# GPRS-Shield-v3_0.net
KiCad netlist of a schematic drawn in EAGLE
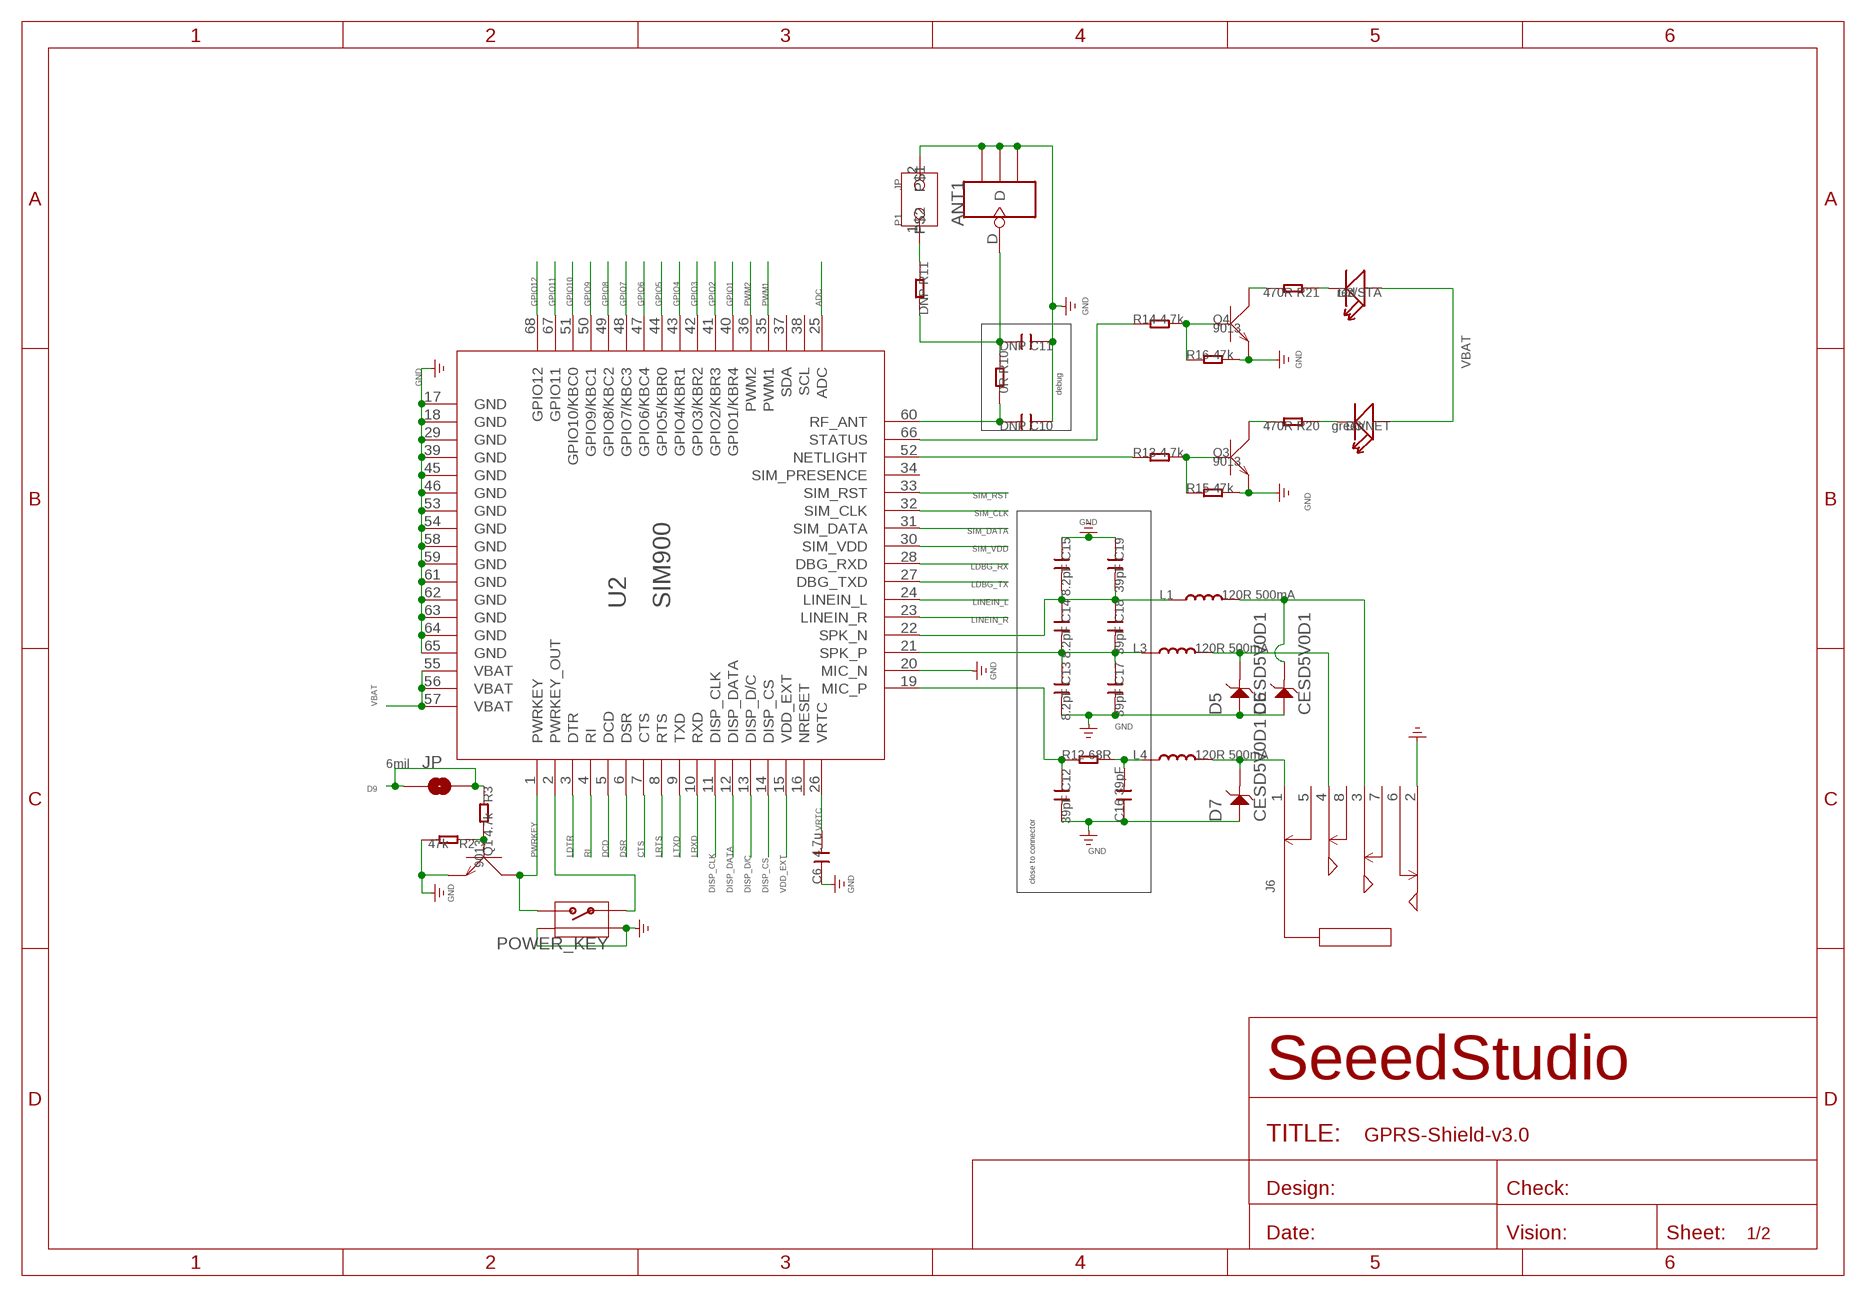
[diagram p0: schematic, sheet 1, part 1 of 2]
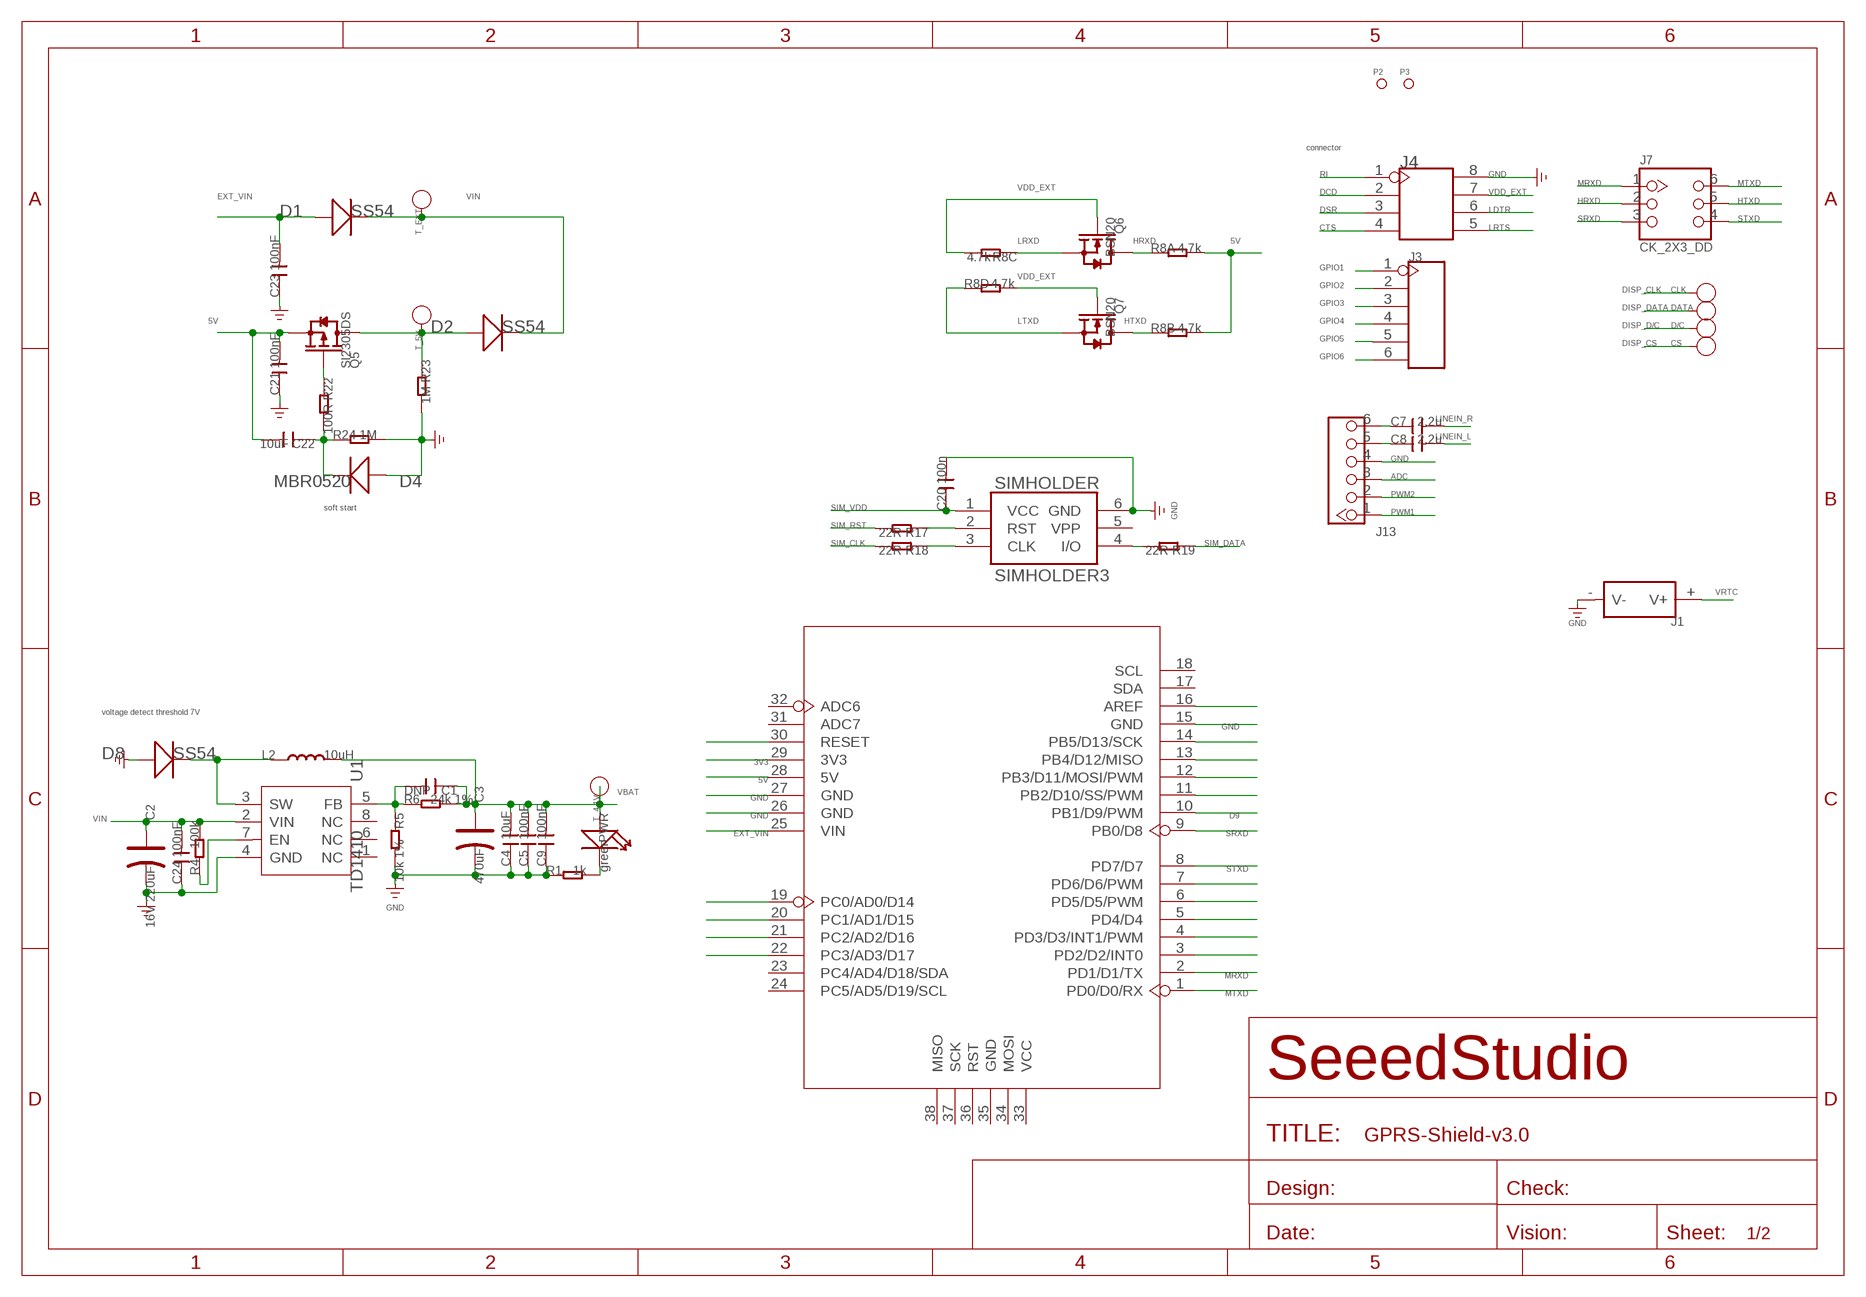
[diagram p1: schematic, sheet 1, part 2 of 2]
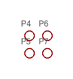
[diagram p2: schematic, sheet 2]

(export (version "E")
  (design (tool "Eeschema 10.0.6"))
  (components
    (comp (ref "ANT1")
      (value "ANTENNA-U-FL")
      (footprint "eagle-import:4P-U-FL")
      (libsource (lib "eagle-import") (part "ANTENNA-U-FL"))
    )
    (comp (ref "C1")
      (value "DNP")
      (footprint "eagle-import:C0603")
      (libsource (lib "eagle-import") (part "C-0603"))
    )
    (comp (ref "C2")
      (value "16V 220uF")
      (footprint "eagle-import:ELECTRO-SMD-D-5.6MM")
      (libsource (lib "eagle-import") (part "CAP-ELECTRO-D"))
    )
    (comp (ref "C3")
      (value "470uF")
      (footprint "eagle-import:AVX-D")
      (libsource (lib "eagle-import") (part "CAP-AVX-D"))
    )
    (comp (ref "C4")
      (value "10uF")
      (footprint "eagle-import:C0805")
      (libsource (lib "eagle-import") (part "C-0805"))
    )
    (comp (ref "C5")
      (value "100nF")
      (footprint "eagle-import:C0603")
      (libsource (lib "eagle-import") (part "C-0603"))
    )
    (comp (ref "C6")
      (value "4.7u")
      (footprint "eagle-import:C0805")
      (libsource (lib "eagle-import") (part "C-0805"))
    )
    (comp (ref "C7")
      (value "2.2u")
      (footprint "eagle-import:C0805")
      (libsource (lib "eagle-import") (part "C-0805"))
    )
    (comp (ref "C8")
      (value "2.2u")
      (footprint "eagle-import:C0805")
      (libsource (lib "eagle-import") (part "C-0805"))
    )
    (comp (ref "C9")
      (value "100nF")
      (footprint "eagle-import:C0603")
      (libsource (lib "eagle-import") (part "C-0603"))
    )
    (comp (ref "C10")
      (value "DNP")
      (footprint "eagle-import:C0603")
      (libsource (lib "eagle-import") (part "C-0603"))
    )
    (comp (ref "C11")
      (value "DNP")
      (footprint "eagle-import:C0603")
      (libsource (lib "eagle-import") (part "C-0603"))
    )
    (comp (ref "C12")
      (value "39pF")
      (footprint "eagle-import:C0603")
      (libsource (lib "eagle-import") (part "C-0603"))
    )
    (comp (ref "C13")
      (value "8.2pF")
      (footprint "eagle-import:C0603")
      (libsource (lib "eagle-import") (part "C-0603"))
    )
    (comp (ref "C14")
      (value "8.2pF")
      (footprint "eagle-import:C0603")
      (libsource (lib "eagle-import") (part "C-0603"))
    )
    (comp (ref "C15")
      (value "8.2pF")
      (footprint "eagle-import:C0603")
      (libsource (lib "eagle-import") (part "C-0603"))
    )
    (comp (ref "C16")
      (value "39pF")
      (footprint "eagle-import:C0603")
      (libsource (lib "eagle-import") (part "C-0603"))
    )
    (comp (ref "C17")
      (value "39pF")
      (footprint "eagle-import:C0603")
      (libsource (lib "eagle-import") (part "C-0603"))
    )
    (comp (ref "C18")
      (value "39pF")
      (footprint "eagle-import:C0603")
      (libsource (lib "eagle-import") (part "C-0603"))
    )
    (comp (ref "C19")
      (value "39pF")
      (footprint "eagle-import:C0603")
      (libsource (lib "eagle-import") (part "C-0603"))
    )
    (comp (ref "C20")
      (value "100n")
      (footprint "eagle-import:C0603")
      (libsource (lib "eagle-import") (part "C-0603"))
    )
    (comp (ref "C21")
      (value "100nF")
      (footprint "eagle-import:C0603")
      (libsource (lib "eagle-import") (part "C-0603"))
    )
    (comp (ref "C22")
      (value "10uF")
      (footprint "eagle-import:C0805")
      (libsource (lib "eagle-import") (part "C-0805"))
    )
    (comp (ref "C23")
      (value "100nF")
      (footprint "eagle-import:C0603")
      (libsource (lib "eagle-import") (part "C-0603"))
    )
    (comp (ref "C24")
      (value "100nF")
      (footprint "eagle-import:C0603")
      (libsource (lib "eagle-import") (part "C-0603"))
    )
    (comp (ref "CLK")
      (value "PAD-TEST-POINT-CIRCLE'4545'")
      (footprint "eagle-import:TP_4545")
      (fields (field (name "PARTNO") "DNP"))
      (libsource (lib "eagle-import") (part "PAD-TEST-POINT-CIRCLE'4545'"))
    )
    (comp (ref "CS")
      (value "PAD-TEST-POINT-CIRCLE'4545'")
      (footprint "eagle-import:TP_4545")
      (fields (field (name "PARTNO") "DNP"))
      (libsource (lib "eagle-import") (part "PAD-TEST-POINT-CIRCLE'4545'"))
    )
    (comp (ref "D/C")
      (value "PAD-TEST-POINT-CIRCLE'4545'")
      (footprint "eagle-import:TP_4545")
      (fields (field (name "PARTNO") "DNP"))
      (libsource (lib "eagle-import") (part "PAD-TEST-POINT-CIRCLE'4545'"))
    )
    (comp (ref "D1")
      (value "SS54")
      (footprint "eagle-import:SMB")
      (libsource (lib "eagle-import") (part "D'MBRS240LT3'"))
    )
    (comp (ref "D2")
      (value "SS54")
      (footprint "eagle-import:SMB")
      (libsource (lib "eagle-import") (part "D'MBRS240LT3'"))
    )
    (comp (ref "D2/STA")
      (value "red")
      (footprint "eagle-import:LED-0603")
      (libsource (lib "eagle-import") (part "LED'0603'"))
    )
    (comp (ref "D3/NET")
      (value "green")
      (footprint "eagle-import:LED-0603")
      (libsource (lib "eagle-import") (part "LED'0603'"))
    )
    (comp (ref "D4")
      (value "MBR0520")
      (footprint "eagle-import:SOD123-2.7X1.6")
      (libsource (lib "eagle-import") (part "D'MBR0520LT1'"))
    )
    (comp (ref "D5")
      (value "CESD5V0D1")
      (footprint "eagle-import:SOD123-2.7X1.6")
      (libsource (lib "eagle-import") (part "D-ESD"))
    )
    (comp (ref "D6")
      (value "CESD5V0D1")
      (footprint "eagle-import:SOD123-2.7X1.6")
      (libsource (lib "eagle-import") (part "D-ESD"))
    )
    (comp (ref "D7")
      (value "CESD5V0D1")
      (footprint "eagle-import:SOD123-2.7X1.6")
      (libsource (lib "eagle-import") (part "D-ESD"))
    )
    (comp (ref "D8")
      (value "SS54")
      (footprint "eagle-import:SMB")
      (libsource (lib "eagle-import") (part "D'MBRS240LT3'"))
    )
    (comp (ref "DATA")
      (value "PAD-TEST-POINT-CIRCLE'4545'")
      (footprint "eagle-import:TP_4545")
      (fields (field (name "PARTNO") "DNP"))
      (libsource (lib "eagle-import") (part "PAD-TEST-POINT-CIRCLE'4545'"))
    )
    (comp (ref "J1")
      (value "HOLDER-BAT")
      (footprint "eagle-import:SMD-CR1220-2")
      (libsource (lib "eagle-import") (part "HOLDER-BAT"))
    )
    (comp (ref "J3")
      (value "HEADER-6P-65/35MIL")
      (footprint "eagle-import:6P-2.54-65_35MIL")
      (libsource (lib "eagle-import") (part "HEADER-6P-65/35MIL"))
    )
    (comp (ref "J4")
      (value "HEADER-2X4P-2.54")
      (footprint "eagle-import:2X4P-2.54")
      (libsource (lib "eagle-import") (part "HEADER-2X4P-2.54"))
    )
    (comp (ref "J6")
      (value "AUDIO-JACK-3.5'PJ-393'")
      (footprint "eagle-import:8P-SMD-3.5")
      (libsource (lib "eagle-import") (part "AUDIO-JACK-3.5'PJ-393'"))
    )
    (comp (ref "J7")
      (value "CK_2X3_DD")
      (footprint "eagle-import:CK_2X3")
      (libsource (lib "eagle-import") (part "CK_2X3_DD"))
    )
    (comp (ref "J13")
      (value "HEADER_1X6")
      (footprint "eagle-import:CK_1X6")
      (libsource (lib "eagle-import") (part "HEADER_1X6"))
    )
    (comp (ref "JP")
      (value "PAD-SOLDERJUMPERNC")
      (footprint "eagle-import:2P-SMD-3.3X2")
      (libsource (lib "eagle-import") (part "PAD-SOLDERJUMPERNC"))
    )
    (comp (ref "L1")
      (value "120R 500mA")
      (footprint "eagle-import:L0603")
      (libsource (lib "eagle-import") (part "L'0603'"))
    )
    (comp (ref "L2")
      (value "10uH")
      (footprint "eagle-import:L0630")
      (libsource (lib "eagle-import") (part "L'0630'"))
    )
    (comp (ref "L3")
      (value "120R 500mA")
      (footprint "eagle-import:L0603")
      (libsource (lib "eagle-import") (part "L'0603'"))
    )
    (comp (ref "L4")
      (value "120R 500mA")
      (footprint "eagle-import:L0603")
      (libsource (lib "eagle-import") (part "L'0603'"))
    )
    (comp (ref "P1") (value "JP") (footprint "eagle-import:JP") (libsource (lib "eagle-import") (part "JP")))
    (comp (ref "P2")
      (value "PAD-MARK")
      (footprint "eagle-import:ROUND-MARK-1.0")
      (fields (field (name "PARTNO") "DNP"))
      (libsource (lib "eagle-import") (part "PAD-MARK"))
    )
    (comp (ref "P3")
      (value "PAD-MARK")
      (footprint "eagle-import:ROUND-MARK-1.0")
      (fields (field (name "PARTNO") "DNP"))
      (libsource (lib "eagle-import") (part "PAD-MARK"))
    )
    (comp (ref "POWER_KEY")
      (value "BUTTON-4P-REINFORCE'TS-118E'")
      (footprint "eagle-import:4P-SMD-7X3.5X3.5H")
      (libsource (lib "eagle-import") (part "BUTTON-4P-REINFORCE'TS-118E'"))
    )
    (comp (ref "PWR")
      (value "green")
      (footprint "eagle-import:D0603")
      (libsource (lib "eagle-import") (part "007-LED0603"))
    )
    (comp (ref "Q1")
      (value "9013")
      (footprint "eagle-import:SOT23")
      (libsource (lib "eagle-import") (part "TRANSISTOR-NPN-SOT23"))
    )
    (comp (ref "Q3")
      (value "9013")
      (footprint "eagle-import:SOT23")
      (libsource (lib "eagle-import") (part "TRANSISTOR-NPN-SOT23"))
    )
    (comp (ref "Q4")
      (value "9013")
      (footprint "eagle-import:SOT23")
      (libsource (lib "eagle-import") (part "TRANSISTOR-NPN-SOT23"))
    )
    (comp (ref "Q5")
      (value "SI2305DS")
      (footprint "eagle-import:SOT23")
      (libsource (lib "eagle-import") (part "MOSFET-P'SI2323CDS/SI2305DS{lt}BR{gt}'"))
    )
    (comp (ref "Q6")
      (value "BSN20")
      (footprint "eagle-import:SOT23")
      (libsource (lib "eagle-import") (part "MOSFET-N'SOT23'"))
    )
    (comp (ref "Q7")
      (value "BSN20")
      (footprint "eagle-import:SOT23")
      (libsource (lib "eagle-import") (part "MOSFET-N'SOT23'"))
    )
    (comp (ref "R1")
      (value "1k")
      (footprint "eagle-import:R0603")
      (libsource (lib "eagle-import") (part "R-0603"))
    )
    (comp (ref "R2")
      (value "47k")
      (footprint "eagle-import:R0603")
      (libsource (lib "eagle-import") (part "R-0603"))
    )
    (comp (ref "R3")
      (value "4.7k")
      (footprint "eagle-import:R0603")
      (libsource (lib "eagle-import") (part "R-0603"))
    )
    (comp (ref "R4")
      (value "100k")
      (footprint "eagle-import:R0603")
      (libsource (lib "eagle-import") (part "R-0603"))
    )
    (comp (ref "R5")
      (value "10k 1%")
      (footprint "eagle-import:R0603")
      (libsource (lib "eagle-import") (part "R-0603"))
    )
    (comp (ref "R6")
      (value "24k 1%")
      (footprint "eagle-import:R0603")
      (libsource (lib "eagle-import") (part "R-0603"))
    )
    (comp (ref "R8")
      (value "4.7k")
      (footprint "eagle-import:1206-8-3.3X2.4")
      (libsource (lib "eagle-import") (part "R-4R-1206"))
    )
    (comp (ref "R10")
      (value "0R")
      (footprint "eagle-import:R0603")
      (libsource (lib "eagle-import") (part "R-0603"))
    )
    (comp (ref "R11")
      (value "DNP")
      (footprint "eagle-import:R0603")
      (libsource (lib "eagle-import") (part "R-0603"))
    )
    (comp (ref "R12")
      (value "68R")
      (footprint "eagle-import:R0603")
      (libsource (lib "eagle-import") (part "R-0603"))
    )
    (comp (ref "R13")
      (value "4.7k")
      (footprint "eagle-import:R0603")
      (libsource (lib "eagle-import") (part "R-0603"))
    )
    (comp (ref "R14")
      (value "4.7k")
      (footprint "eagle-import:R0603")
      (libsource (lib "eagle-import") (part "R-0603"))
    )
    (comp (ref "R15")
      (value "47k")
      (footprint "eagle-import:R0603")
      (libsource (lib "eagle-import") (part "R-0603"))
    )
    (comp (ref "R16")
      (value "47k")
      (footprint "eagle-import:R0603")
      (libsource (lib "eagle-import") (part "R-0603"))
    )
    (comp (ref "R17")
      (value "22R")
      (footprint "eagle-import:R0603")
      (libsource (lib "eagle-import") (part "R-0603"))
    )
    (comp (ref "R18")
      (value "22R")
      (footprint "eagle-import:R0603")
      (libsource (lib "eagle-import") (part "R-0603"))
    )
    (comp (ref "R19")
      (value "22R")
      (footprint "eagle-import:R0603")
      (libsource (lib "eagle-import") (part "R-0603"))
    )
    (comp (ref "R20")
      (value "470R")
      (footprint "eagle-import:R0603")
      (libsource (lib "eagle-import") (part "R-0603"))
    )
    (comp (ref "R21")
      (value "470R")
      (footprint "eagle-import:R0603")
      (libsource (lib "eagle-import") (part "R-0603"))
    )
    (comp (ref "R22")
      (value "100R")
      (footprint "eagle-import:R0603")
      (libsource (lib "eagle-import") (part "R-0603"))
    )
    (comp (ref "R23")
      (value "1M")
      (footprint "eagle-import:R0603")
      (libsource (lib "eagle-import") (part "R-0603"))
    )
    (comp (ref "R24")
      (value "1M")
      (footprint "eagle-import:R0603")
      (libsource (lib "eagle-import") (part "R-0603"))
    )
    (comp (ref "SIMHOLDER")
      (value "SIMHOLDER3")
      (footprint "eagle-import:SIMHOLDER3")
      (libsource (lib "eagle-import") (part "SIMHOLDER3"))
    )
    (comp (ref "T_4.1V")
      (value "PAD-TEST-POINT-CIRCLE'4545'")
      (footprint "eagle-import:TP_4545")
      (fields (field (name "PARTNO") "DNP") (field (name "PARTNO_1") "DNP"))
      (libsource (lib "eagle-import") (part "PAD-TEST-POINT-CIRCLE'4545'"))
    )
    (comp (ref "T_5V")
      (value "PAD-TEST-POINT-CIRCLE'4545'")
      (footprint "eagle-import:TP_4545")
      (fields (field (name "PARTNO") "DNP") (field (name "PARTNO_1") "DNP"))
      (libsource (lib "eagle-import") (part "PAD-TEST-POINT-CIRCLE'4545'"))
    )
    (comp (ref "T_EXT")
      (value "PAD-TEST-POINT-CIRCLE'4545'")
      (footprint "eagle-import:TP_4545")
      (fields (field (name "PARTNO") "DNP") (field (name "PARTNO_1") "DNP"))
      (libsource (lib "eagle-import") (part "PAD-TEST-POINT-CIRCLE'4545'"))
    )
    (comp (ref "U1")
      (value "TD1410")
      (footprint "eagle-import:SOP8")
      (libsource (lib "eagle-import") (part "TD1410"))
    )
    (comp (ref "U2")
      (value "SIM900")
      (footprint "eagle-import:SIM900")
      (libsource (lib "eagle-import") (part "SIM900"))
    )
    (comp (ref "U4")
      (value "ARDUINO-38P'WITH/O-SILK'")
      (footprint "eagle-import:ARDUINO-38P-500519002")
      (libsource (lib "eagle-import") (part "ARDUINO-38P'WITH/O-SILK'"))
    )
    (comp (ref "P4")
      (value "PAD-MARK")
      (footprint "eagle-import:ROUND-MARK-1.0")
      (fields (field (name "PARTNO") "DNP"))
      (libsource (lib "eagle-import") (part "PAD-MARK"))
    )
    (comp (ref "P5")
      (value "PAD-MARK")
      (footprint "eagle-import:ROUND-MARK-1.0")
      (fields (field (name "PARTNO") "DNP"))
      (libsource (lib "eagle-import") (part "PAD-MARK"))
    )
    (comp (ref "P6")
      (value "PAD-MARK")
      (footprint "eagle-import:ROUND-MARK-1.0")
      (fields (field (name "PARTNO") "DNP"))
      (libsource (lib "eagle-import") (part "PAD-MARK"))
    )
    (comp (ref "P7")
      (value "PAD-MARK")
      (footprint "eagle-import:ROUND-MARK-1.0")
      (fields (field (name "PARTNO") "DNP"))
      (libsource (lib "eagle-import") (part "PAD-MARK"))
    )
  )
  (nets
    (net (code "1") (name "3V3") (class "Default")
      (node (ref "U4") (pin "29") (pinfunction "3V3_29") (pintype "bidirectional"))
    )
    (net (code "2") (name "5V") (class "Default")
      (node (ref "C21") (pin "2") (pinfunction "2_2") (pintype "passive"))
      (node (ref "C22") (pin "2") (pinfunction "2_2") (pintype "passive"))
      (node (ref "Q5") (pin "2") (pinfunction "S_2") (pintype "passive"))
      (node (ref "R8") (pin "7") (pinfunction "2_7") (pintype "passive"))
      (node (ref "R8") (pin "8") (pinfunction "2_8") (pintype "passive"))
      (node (ref "U4") (pin "28") (pinfunction "5V_28") (pintype "bidirectional"))
    )
    (net (code "3") (name "ADC") (class "Default")
      (node (ref "J13") (pin "3") (pinfunction "3_3") (pintype "bidirectional"))
      (node (ref "U2") (pin "25") (pinfunction "ADC_25") (pintype "input"))
    )
    (net (code "4") (name "CTS") (class "Default")
      (node (ref "J4") (pin "4") (pinfunction "4_4") (pintype "bidirectional"))
      (node (ref "U2") (pin "7") (pinfunction "CTS_7") (pintype "output"))
    )
    (net (code "5") (name "D9") (class "Default")
      (node (ref "JP") (pin "1") (pinfunction "1_1") (pintype "passive"))
      (node (ref "JP") (pin "2") (pinfunction "2_2") (pintype "passive"))
      (node (ref "R3") (pin "1") (pinfunction "1_1") (pintype "passive"))
      (node (ref "U4") (pin "10") (pinfunction "PB1/D9/PWM_10") (pintype "bidirectional"))
    )
    (net (code "6") (name "DCD") (class "Default")
      (node (ref "J4") (pin "2") (pinfunction "2_2") (pintype "bidirectional"))
      (node (ref "U2") (pin "5") (pinfunction "DCD_5") (pintype "output"))
    )
    (net (code "7") (name "DISP_CLK") (class "Default")
      (node (ref "CLK") (pin "T") (pinfunction "T_T") (pintype "bidirectional"))
      (node (ref "U2") (pin "11") (pinfunction "DISP_CLK_11") (pintype "output"))
    )
    (net (code "8") (name "DISP_CS") (class "Default")
      (node (ref "CS") (pin "T") (pinfunction "T_T") (pintype "bidirectional"))
      (node (ref "U2") (pin "14") (pinfunction "DISP_CS_14") (pintype "output"))
    )
    (net (code "9") (name "DISP_DATA") (class "Default")
      (node (ref "DATA") (pin "T") (pinfunction "T_T") (pintype "bidirectional"))
      (node (ref "U2") (pin "12") (pinfunction "DISP_DATA_12") (pintype "bidirectional"))
    )
    (net (code "10") (name "DISP_D{slash}C") (class "Default")
      (node (ref "D/C") (pin "T") (pinfunction "T_T") (pintype "bidirectional"))
      (node (ref "U2") (pin "13") (pinfunction "DISP_D/C_13") (pintype "output"))
    )
    (net (code "11") (name "DSR") (class "Default")
      (node (ref "J4") (pin "3") (pinfunction "3_3") (pintype "bidirectional"))
      (node (ref "U2") (pin "6") (pinfunction "DSR_6") (pintype "output"))
    )
    (net (code "12") (name "EXT_VIN") (class "Default")
      (node (ref "C23") (pin "2") (pinfunction "2_2") (pintype "passive"))
      (node (ref "D1") (pin "+") (pinfunction "+_+") (pintype "passive"))
      (node (ref "U4") (pin "25") (pinfunction "VIN_25") (pintype "bidirectional"))
    )
    (net (code "13") (name "GND") (class "Default")
      (node (ref "ANT1") (pin "GND1") (pinfunction "GND1_GND1") (pintype "bidirectional"))
      (node (ref "ANT1") (pin "GND2") (pinfunction "GND2_GND2") (pintype "bidirectional"))
      (node (ref "ANT1") (pin "GND3") (pinfunction "GND3_GND3") (pintype "bidirectional"))
      (node (ref "C10") (pin "1") (pinfunction "1_1") (pintype "passive"))
      (node (ref "C11") (pin "1") (pinfunction "1_1") (pintype "passive"))
      (node (ref "C12") (pin "2") (pinfunction "2_2") (pintype "passive"))
      (node (ref "C13") (pin "2") (pinfunction "2_2") (pintype "passive"))
      (node (ref "C15") (pin "1") (pinfunction "1_1") (pintype "passive"))
      (node (ref "C16") (pin "1") (pinfunction "1_1") (pintype "passive"))
      (node (ref "C17") (pin "2") (pinfunction "2_2") (pintype "passive"))
      (node (ref "C19") (pin "1") (pinfunction "1_1") (pintype "passive"))
      (node (ref "C2") (pin "-") (pinfunction "-_-") (pintype "passive"))
      (node (ref "C20") (pin "2") (pinfunction "2_2") (pintype "passive"))
      (node (ref "C21") (pin "1") (pinfunction "1_1") (pintype "passive"))
      (node (ref "C23") (pin "1") (pinfunction "1_1") (pintype "passive"))
      (node (ref "C24") (pin "1") (pinfunction "1_1") (pintype "passive"))
      (node (ref "C3") (pin "-") (pinfunction "-_-") (pintype "passive"))
      (node (ref "C4") (pin "1") (pinfunction "1_1") (pintype "passive"))
      (node (ref "C5") (pin "1") (pinfunction "1_1") (pintype "passive"))
      (node (ref "C6") (pin "1") (pinfunction "1_1") (pintype "passive"))
      (node (ref "C9") (pin "1") (pinfunction "1_1") (pintype "passive"))
      (node (ref "D4") (pin "1") (pinfunction "+_1") (pintype "passive"))
      (node (ref "D5") (pin "1") (pinfunction "1_1") (pintype "bidirectional"))
      (node (ref "D6") (pin "1") (pinfunction "1_1") (pintype "bidirectional"))
      (node (ref "D7") (pin "1") (pinfunction "1_1") (pintype "bidirectional"))
      (node (ref "D8") (pin "+") (pinfunction "+_+") (pintype "passive"))
      (node (ref "J1") (pin "-") (pinfunction "V-_-") (pintype "bidirectional"))
      (node (ref "J13") (pin "4") (pinfunction "4_4") (pintype "bidirectional"))
      (node (ref "J4") (pin "8") (pinfunction "8_8") (pintype "bidirectional"))
      (node (ref "J6") (pin "2") (pinfunction "2_2") (pintype "bidirectional"))
      (node (ref "P1") (pin "2") (pinfunction "P$2_2") (pintype "bidirectional"))
      (node (ref "POWER_KEY") (pin "S1") (pinfunction "S1_S1") (pintype "bidirectional"))
      (node (ref "POWER_KEY") (pin "S2") (pinfunction "S2_S2") (pintype "bidirectional"))
      (node (ref "Q1") (pin "2") (pinfunction "E_2") (pintype "passive"))
      (node (ref "Q3") (pin "2") (pinfunction "E_2") (pintype "passive"))
      (node (ref "Q4") (pin "2") (pinfunction "E_2") (pintype "passive"))
      (node (ref "R1") (pin "1") (pinfunction "1_1") (pintype "passive"))
      (node (ref "R15") (pin "2") (pinfunction "2_2") (pintype "passive"))
      (node (ref "R16") (pin "2") (pinfunction "2_2") (pintype "passive"))
      (node (ref "R2") (pin "2") (pinfunction "2_2") (pintype "passive"))
      (node (ref "R23") (pin "2") (pinfunction "2_2") (pintype "passive"))
      (node (ref "R24") (pin "2") (pinfunction "2_2") (pintype "passive"))
      (node (ref "R5") (pin "2") (pinfunction "2_2") (pintype "passive"))
      (node (ref "SIMHOLDER") (pin "6") (pinfunction "GND_6") (pintype "bidirectional"))
      (node (ref "U1") (pin "4") (pinfunction "GND_4") (pintype "power_in"))
      (node (ref "U2") (pin "17") (pinfunction "GND_17") (pintype "power_in"))
      (node (ref "U2") (pin "18") (pinfunction "GND_18") (pintype "power_in"))
      (node (ref "U2") (pin "20") (pinfunction "MIC_N_20") (pintype "input"))
      (node (ref "U2") (pin "29") (pinfunction "GND_29") (pintype "power_in"))
      (node (ref "U2") (pin "39") (pinfunction "GND_39") (pintype "power_in"))
      (node (ref "U2") (pin "45") (pinfunction "GND_45") (pintype "power_in"))
      (node (ref "U2") (pin "46") (pinfunction "GND_46") (pintype "power_in"))
      (node (ref "U2") (pin "53") (pinfunction "GND_53") (pintype "power_in"))
      (node (ref "U2") (pin "54") (pinfunction "GND_54") (pintype "power_in"))
      (node (ref "U2") (pin "58") (pinfunction "GND_58") (pintype "power_in"))
      (node (ref "U2") (pin "59") (pinfunction "GND_59") (pintype "power_in"))
      (node (ref "U2") (pin "61") (pinfunction "GND_61") (pintype "power_in"))
      (node (ref "U2") (pin "62") (pinfunction "GND_62") (pintype "power_in"))
      (node (ref "U2") (pin "63") (pinfunction "GND_63") (pintype "power_in"))
      (node (ref "U2") (pin "64") (pinfunction "GND_64") (pintype "power_in"))
      (node (ref "U2") (pin "65") (pinfunction "GND_65") (pintype "power_in"))
      (node (ref "U4") (pin "15") (pinfunction "GND_15") (pintype "bidirectional"))
      (node (ref "U4") (pin "26") (pinfunction "GND_26") (pintype "bidirectional"))
      (node (ref "U4") (pin "27") (pinfunction "GND_27") (pintype "bidirectional"))
    )
    (net (code "14") (name "GPIO1") (class "Default")
      (node (ref "J3") (pin "1") (pinfunction "1_1") (pintype "bidirectional"))
      (node (ref "U2") (pin "40") (pinfunction "GPIO1/KBR4_40") (pintype "output"))
    )
    (net (code "15") (name "GPIO2") (class "Default")
      (node (ref "J3") (pin "2") (pinfunction "2_2") (pintype "bidirectional"))
      (node (ref "U2") (pin "41") (pinfunction "GPIO2/KBR3_41") (pintype "output"))
    )
    (net (code "16") (name "GPIO3") (class "Default")
      (node (ref "J3") (pin "3") (pinfunction "3_3") (pintype "bidirectional"))
      (node (ref "U2") (pin "42") (pinfunction "GPIO3/KBR2_42") (pintype "output"))
    )
    (net (code "17") (name "GPIO4") (class "Default")
      (node (ref "J3") (pin "4") (pinfunction "4_4") (pintype "bidirectional"))
      (node (ref "U2") (pin "43") (pinfunction "GPIO4/KBR1_43") (pintype "output"))
    )
    (net (code "18") (name "GPIO5") (class "Default")
      (node (ref "J3") (pin "5") (pinfunction "5_5") (pintype "bidirectional"))
      (node (ref "U2") (pin "44") (pinfunction "GPIO5/KBR0_44") (pintype "output"))
    )
    (net (code "19") (name "GPIO6") (class "Default")
      (node (ref "J3") (pin "6") (pinfunction "6_6") (pintype "bidirectional"))
      (node (ref "U2") (pin "47") (pinfunction "GPIO6/KBC4_47") (pintype "input"))
    )
    (net (code "20") (name "GPIO7") (class "Default")
      (node (ref "U2") (pin "48") (pinfunction "GPIO7/KBC3_48") (pintype "bidirectional"))
    )
    (net (code "21") (name "GPIO8") (class "Default")
      (node (ref "U2") (pin "49") (pinfunction "GPIO8/KBC2_49") (pintype "input"))
    )
    (net (code "22") (name "GPIO9") (class "Default")
      (node (ref "U2") (pin "50") (pinfunction "GPIO9/KBC1_50") (pintype "input"))
    )
    (net (code "23") (name "GPIO10") (class "Default")
      (node (ref "U2") (pin "51") (pinfunction "GPIO10/KBC0_51") (pintype "bidirectional"))
    )
    (net (code "24") (name "GPIO11") (class "Default")
      (node (ref "U2") (pin "67") (pinfunction "GPIO11_67") (pintype "bidirectional"))
    )
    (net (code "25") (name "GPIO12") (class "Default")
      (node (ref "U2") (pin "68") (pinfunction "GPIO12_68") (pintype "bidirectional"))
    )
    (net (code "26") (name "HRXD") (class "Default")
      (node (ref "J7") (pin "2") (pinfunction "2_2") (pintype "bidirectional"))
      (node (ref "Q6") (pin "3") (pinfunction "D_3") (pintype "passive"))
      (node (ref "R8") (pin "1") (pinfunction "1_1") (pintype "passive"))
    )
    (net (code "27") (name "HTXD") (class "Default")
      (node (ref "J7") (pin "5") (pinfunction "5_5") (pintype "bidirectional"))
      (node (ref "Q7") (pin "3") (pinfunction "D_3") (pintype "passive"))
      (node (ref "R8") (pin "2") (pinfunction "1_2") (pintype "passive"))
    )
    (net (code "28") (name "LDBG_RX") (class "Default")
      (node (ref "U2") (pin "28") (pinfunction "DBG_RXD_28") (pintype "input"))
    )
    (net (code "29") (name "LDBG_TX") (class "Default")
      (node (ref "U2") (pin "27") (pinfunction "DBG_TXD_27") (pintype "output"))
    )
    (net (code "30") (name "LDTR") (class "Default")
      (node (ref "J4") (pin "6") (pinfunction "6_6") (pintype "bidirectional"))
      (node (ref "U2") (pin "3") (pinfunction "DTR_3") (pintype "input"))
    )
    (net (code "31") (name "LINEIN_L") (class "Default")
      (node (ref "C8") (pin "2") (pinfunction "2_2") (pintype "passive"))
      (node (ref "U2") (pin "24") (pinfunction "LINEIN_L_24") (pintype "input"))
    )
    (net (code "32") (name "LINEIN_R") (class "Default")
      (node (ref "C7") (pin "2") (pinfunction "2_2") (pintype "passive"))
      (node (ref "U2") (pin "23") (pinfunction "LINEIN_R_23") (pintype "input"))
    )
    (net (code "33") (name "LRTS") (class "Default")
      (node (ref "J4") (pin "5") (pinfunction "5_5") (pintype "bidirectional"))
      (node (ref "U2") (pin "8") (pinfunction "RTS_8") (pintype "input"))
    )
    (net (code "34") (name "LRXD") (class "Default")
      (node (ref "Q6") (pin "2") (pinfunction "S_2") (pintype "passive"))
      (node (ref "R8") (pin "3") (pinfunction "1_3") (pintype "passive"))
      (node (ref "U2") (pin "10") (pinfunction "RXD_10") (pintype "input"))
    )
    (net (code "35") (name "LTXD") (class "Default")
      (node (ref "Q7") (pin "2") (pinfunction "S_2") (pintype "passive"))
      (node (ref "R8") (pin "4") (pinfunction "1_4") (pintype "passive"))
      (node (ref "U2") (pin "9") (pinfunction "TXD_9") (pintype "output"))
    )
    (net (code "36") (name "MRXD") (class "Default")
      (node (ref "J7") (pin "1") (pinfunction "1_1") (pintype "bidirectional"))
      (node (ref "U4") (pin "2") (pinfunction "PD1/D1/TX_2") (pintype "bidirectional"))
    )
    (net (code "37") (name "MTXD") (class "Default")
      (node (ref "J7") (pin "6") (pinfunction "6_6") (pintype "bidirectional"))
      (node (ref "U4") (pin "1") (pinfunction "PD0/D0/RX_1") (pintype "bidirectional"))
    )
    (net (code "38") (name "Net-(ANT1-PadD)") (class "Default")
      (node (ref "ANT1") (pin "D") (pinfunction "D_D") (pintype "bidirectional"))
      (node (ref "C11") (pin "2") (pinfunction "2_2") (pintype "passive"))
      (node (ref "R10") (pin "1") (pinfunction "1_1") (pintype "passive"))
      (node (ref "R11") (pin "2") (pinfunction "2_2") (pintype "passive"))
    )
    (net (code "39") (name "Net-(C7-Pad1)") (class "Default")
      (node (ref "C7") (pin "1") (pinfunction "1_1") (pintype "passive"))
      (node (ref "J13") (pin "6") (pinfunction "6_6") (pintype "bidirectional"))
    )
    (net (code "40") (name "Net-(C8-Pad1)") (class "Default")
      (node (ref "C8") (pin "1") (pinfunction "1_1") (pintype "passive"))
      (node (ref "J13") (pin "5") (pinfunction "5_5") (pintype "bidirectional"))
    )
    (net (code "41") (name "Net-(C16-Pad2)") (class "Default")
      (node (ref "C16") (pin "2") (pinfunction "2_2") (pintype "passive"))
      (node (ref "L4") (pin "1") (pinfunction "1_1") (pintype "passive"))
      (node (ref "R12") (pin "2") (pinfunction "2_2") (pintype "passive"))
    )
    (net (code "42") (name "Net-(D2/STA-Pad-)") (class "Default")
      (node (ref "D2/STA") (pin "-") (pinfunction "-_-") (pintype "passive"))
      (node (ref "R21") (pin "1") (pinfunction "1_1") (pintype "passive"))
    )
    (net (code "43") (name "Net-(D3/NET-Pad-)") (class "Default")
      (node (ref "D3/NET") (pin "-") (pinfunction "-_-") (pintype "passive"))
      (node (ref "R20") (pin "1") (pinfunction "1_1") (pintype "passive"))
    )
    (net (code "44") (name "Net-(D4--)") (class "Default")
      (node (ref "C22") (pin "1") (pinfunction "1_1") (pintype "passive"))
      (node (ref "D4") (pin "2") (pinfunction "-_2") (pintype "passive"))
      (node (ref "R22") (pin "2") (pinfunction "2_2") (pintype "passive"))
      (node (ref "R24") (pin "1") (pinfunction "1_1") (pintype "passive"))
    )
    (net (code "45") (name "Net-(D5-Pad2)") (class "Default")
      (node (ref "D5") (pin "2") (pinfunction "2_2") (pintype "bidirectional"))
      (node (ref "J6") (pin "4") (pinfunction "4_4") (pintype "bidirectional"))
      (node (ref "L3") (pin "2") (pinfunction "2_2") (pintype "passive"))
    )
    (net (code "46") (name "Net-(D6-Pad2)") (class "Default")
      (node (ref "D6") (pin "2") (pinfunction "2_2") (pintype "bidirectional"))
      (node (ref "J6") (pin "3") (pinfunction "3_3") (pintype "bidirectional"))
      (node (ref "L1") (pin "2") (pinfunction "2_2") (pintype "passive"))
    )
    (net (code "47") (name "Net-(D7-Pad2)") (class "Default")
      (node (ref "D7") (pin "2") (pinfunction "2_2") (pintype "bidirectional"))
      (node (ref "J6") (pin "1") (pinfunction "1_1") (pintype "bidirectional"))
      (node (ref "L4") (pin "2") (pinfunction "2_2") (pintype "passive"))
    )
    (net (code "48") (name "Net-(P1-P$1)") (class "Default")
      (node (ref "P1") (pin "1") (pinfunction "P$1_1") (pintype "bidirectional"))
      (node (ref "R11") (pin "1") (pinfunction "1_1") (pintype "passive"))
    )
    (net (code "49") (name "Net-(PWR-Pad-)") (class "Default")
      (node (ref "PWR") (pin "-") (pinfunction "-_-") (pintype "passive"))
      (node (ref "R1") (pin "2") (pinfunction "2_2") (pintype "passive"))
    )
    (net (code "50") (name "Net-(Q1-B)") (class "Default")
      (node (ref "Q1") (pin "1") (pinfunction "B_1") (pintype "passive"))
      (node (ref "R2") (pin "1") (pinfunction "1_1") (pintype "passive"))
      (node (ref "R3") (pin "2") (pinfunction "2_2") (pintype "passive"))
    )
    (net (code "51") (name "Net-(Q3-B)") (class "Default")
      (node (ref "Q3") (pin "1") (pinfunction "B_1") (pintype "passive"))
      (node (ref "R13") (pin "2") (pinfunction "2_2") (pintype "passive"))
      (node (ref "R15") (pin "1") (pinfunction "1_1") (pintype "passive"))
    )
    (net (code "52") (name "Net-(Q3-C)") (class "Default")
      (node (ref "Q3") (pin "3") (pinfunction "C_3") (pintype "passive"))
      (node (ref "R20") (pin "2") (pinfunction "2_2") (pintype "passive"))
    )
    (net (code "53") (name "Net-(Q4-B)") (class "Default")
      (node (ref "Q4") (pin "1") (pinfunction "B_1") (pintype "passive"))
      (node (ref "R14") (pin "2") (pinfunction "2_2") (pintype "passive"))
      (node (ref "R16") (pin "1") (pinfunction "1_1") (pintype "passive"))
    )
    (net (code "54") (name "Net-(Q4-C)") (class "Default")
      (node (ref "Q4") (pin "3") (pinfunction "C_3") (pintype "passive"))
      (node (ref "R21") (pin "2") (pinfunction "2_2") (pintype "passive"))
    )
    (net (code "55") (name "Net-(Q5-D)") (class "Default")
      (node (ref "D2") (pin "+") (pinfunction "+_+") (pintype "passive"))
      (node (ref "Q5") (pin "3") (pinfunction "D_3") (pintype "passive"))
      (node (ref "R23") (pin "1") (pinfunction "1_1") (pintype "passive"))
      (node (ref "T_5V") (pin "T") (pinfunction "T_T") (pintype "bidirectional"))
    )
    (net (code "56") (name "Net-(Q5-G)") (class "Default")
      (node (ref "Q5") (pin "1") (pinfunction "G_1") (pintype "passive"))
      (node (ref "R22") (pin "1") (pinfunction "1_1") (pintype "passive"))
    )
    (net (code "57") (name "Net-(SIMHOLDER-CLK)") (class "Default")
      (node (ref "R18") (pin "1") (pinfunction "1_1") (pintype "passive"))
      (node (ref "SIMHOLDER") (pin "3") (pinfunction "CLK_3") (pintype "bidirectional"))
    )
    (net (code "58") (name "Net-(SIMHOLDER-I{slash}O)") (class "Default")
      (node (ref "R19") (pin "2") (pinfunction "2_2") (pintype "passive"))
      (node (ref "SIMHOLDER") (pin "4") (pinfunction "I/O_4") (pintype "bidirectional"))
    )
    (net (code "59") (name "Net-(SIMHOLDER-RST)") (class "Default")
      (node (ref "R17") (pin "1") (pinfunction "1_1") (pintype "passive"))
      (node (ref "SIMHOLDER") (pin "2") (pinfunction "RST_2") (pintype "bidirectional"))
    )
    (net (code "60") (name "Net-(U1-EN)") (class "Default")
      (node (ref "R4") (pin "1") (pinfunction "1_1") (pintype "passive"))
      (node (ref "U1") (pin "7") (pinfunction "EN_7") (pintype "input"))
    )
    (net (code "61") (name "Net-(U1-FB)") (class "Default")
      (node (ref "C1") (pin "2") (pinfunction "2_2") (pintype "passive"))
      (node (ref "R5") (pin "1") (pinfunction "1_1") (pintype "passive"))
      (node (ref "R6") (pin "1") (pinfunction "1_1") (pintype "passive"))
      (node (ref "U1") (pin "5") (pinfunction "FB_5") (pintype "input"))
    )
    (net (code "62") (name "Net-(U1-SW)") (class "Default")
      (node (ref "D8") (pin "-") (pinfunction "-_-") (pintype "passive"))
      (node (ref "L2") (pin "1") (pinfunction "1_1") (pintype "passive"))
      (node (ref "U1") (pin "3") (pinfunction "SW_3") (pintype "output"))
    )
    (net (code "63") (name "Net-(U2-MIC_P)") (class "Default")
      (node (ref "C12") (pin "1") (pinfunction "1_1") (pintype "passive"))
      (node (ref "R12") (pin "1") (pinfunction "1_1") (pintype "passive"))
      (node (ref "U2") (pin "19") (pinfunction "MIC_P_19") (pintype "input"))
    )
    (net (code "64") (name "Net-(U2-NETLIGHT)") (class "Default")
      (node (ref "R13") (pin "1") (pinfunction "1_1") (pintype "passive"))
      (node (ref "U2") (pin "52") (pinfunction "NETLIGHT_52") (pintype "output"))
    )
    (net (code "65") (name "Net-(U2-PWRKEY_OUT)") (class "Default")
      (node (ref "POWER_KEY") (pin "1") (pinfunction "1_1") (pintype "bidirectional"))
      (node (ref "U2") (pin "2") (pinfunction "PWRKEY_OUT_2") (pintype "output"))
    )
    (net (code "66") (name "Net-(U2-RF_ANT)") (class "Default")
      (node (ref "C10") (pin "2") (pinfunction "2_2") (pintype "passive"))
      (node (ref "R10") (pin "2") (pinfunction "2_2") (pintype "passive"))
      (node (ref "U2") (pin "60") (pinfunction "RF_ANT_60") (pintype "bidirectional"))
    )
    (net (code "67") (name "Net-(U2-SPK_N)") (class "Default")
      (node (ref "C14") (pin "1") (pinfunction "1_1") (pintype "passive"))
      (node (ref "C15") (pin "2") (pinfunction "2_2") (pintype "passive"))
      (node (ref "C18") (pin "1") (pinfunction "1_1") (pintype "passive"))
      (node (ref "C19") (pin "2") (pinfunction "2_2") (pintype "passive"))
      (node (ref "L1") (pin "1") (pinfunction "1_1") (pintype "passive"))
      (node (ref "U2") (pin "22") (pinfunction "SPK_N_22") (pintype "output"))
    )
    (net (code "68") (name "Net-(U2-SPK_P)") (class "Default")
      (node (ref "C13") (pin "1") (pinfunction "1_1") (pintype "passive"))
      (node (ref "C14") (pin "2") (pinfunction "2_2") (pintype "passive"))
      (node (ref "C17") (pin "1") (pinfunction "1_1") (pintype "passive"))
      (node (ref "C18") (pin "2") (pinfunction "2_2") (pintype "passive"))
      (node (ref "L3") (pin "1") (pinfunction "1_1") (pintype "passive"))
      (node (ref "U2") (pin "21") (pinfunction "SPK_P_21") (pintype "output"))
    )
    (net (code "69") (name "Net-(U2-STATUS)") (class "Default")
      (node (ref "R14") (pin "1") (pinfunction "1_1") (pintype "passive"))
      (node (ref "U2") (pin "66") (pinfunction "STATUS_66") (pintype "output"))
    )
    (net (code "70") (name "PWM1") (class "Default")
      (node (ref "J13") (pin "1") (pinfunction "1_1") (pintype "bidirectional"))
      (node (ref "U2") (pin "35") (pinfunction "PWM1_35") (pintype "output"))
    )
    (net (code "71") (name "PWM2") (class "Default")
      (node (ref "J13") (pin "2") (pinfunction "2_2") (pintype "bidirectional"))
      (node (ref "U2") (pin "36") (pinfunction "PWM2_36") (pintype "output"))
    )
    (net (code "72") (name "PWRKEY") (class "Default")
      (node (ref "POWER_KEY") (pin "2") (pinfunction "2_2") (pintype "bidirectional"))
      (node (ref "Q1") (pin "3") (pinfunction "C_3") (pintype "passive"))
      (node (ref "U2") (pin "1") (pinfunction "PWRKEY_1") (pintype "input"))
    )
    (net (code "73") (name "RI") (class "Default")
      (node (ref "J4") (pin "1") (pinfunction "1_1") (pintype "bidirectional"))
      (node (ref "U2") (pin "4") (pinfunction "RI_4") (pintype "output"))
    )
    (net (code "74") (name "SIM_CLK") (class "Default")
      (node (ref "R18") (pin "2") (pinfunction "2_2") (pintype "passive"))
      (node (ref "U2") (pin "32") (pinfunction "SIM_CLK_32") (pintype "output"))
    )
    (net (code "75") (name "SIM_DATA") (class "Default")
      (node (ref "R19") (pin "1") (pinfunction "1_1") (pintype "passive"))
      (node (ref "U2") (pin "31") (pinfunction "SIM_DATA_31") (pintype "bidirectional"))
    )
    (net (code "76") (name "SIM_RST") (class "Default")
      (node (ref "R17") (pin "2") (pinfunction "2_2") (pintype "passive"))
      (node (ref "U2") (pin "33") (pinfunction "SIM_RST_33") (pintype "output"))
    )
    (net (code "77") (name "SIM_VDD") (class "Default")
      (node (ref "C20") (pin "1") (pinfunction "1_1") (pintype "passive"))
      (node (ref "SIMHOLDER") (pin "1") (pinfunction "VCC_1") (pintype "bidirectional"))
      (node (ref "U2") (pin "30") (pinfunction "SIM_VDD_30") (pintype "output"))
    )
    (net (code "78") (name "SRXD") (class "Default")
      (node (ref "J7") (pin "3") (pinfunction "3_3") (pintype "bidirectional"))
      (node (ref "U4") (pin "9") (pinfunction "PB0/D8_9") (pintype "bidirectional"))
    )
    (net (code "79") (name "STXD") (class "Default")
      (node (ref "J7") (pin "4") (pinfunction "4_4") (pintype "bidirectional"))
      (node (ref "U4") (pin "8") (pinfunction "PD7/D7_8") (pintype "bidirectional"))
    )
    (net (code "80") (name "VBAT") (class "Default")
      (node (ref "C1") (pin "1") (pinfunction "1_1") (pintype "passive"))
      (node (ref "C3") (pin "+") (pinfunction "+_+") (pintype "passive"))
      (node (ref "C4") (pin "2") (pinfunction "2_2") (pintype "passive"))
      (node (ref "C5") (pin "2") (pinfunction "2_2") (pintype "passive"))
      (node (ref "C9") (pin "2") (pinfunction "2_2") (pintype "passive"))
      (node (ref "D2/STA") (pin "+") (pinfunction "+_+") (pintype "passive"))
      (node (ref "D3/NET") (pin "+") (pinfunction "+_+") (pintype "passive"))
      (node (ref "L2") (pin "2") (pinfunction "2_2") (pintype "passive"))
      (node (ref "PWR") (pin "+") (pinfunction "+_+") (pintype "passive"))
      (node (ref "R6") (pin "2") (pinfunction "2_2") (pintype "passive"))
      (node (ref "T_4.1V") (pin "T") (pinfunction "T_T") (pintype "bidirectional"))
      (node (ref "U2") (pin "55") (pinfunction "VBAT_55") (pintype "power_in"))
      (node (ref "U2") (pin "56") (pinfunction "VBAT_56") (pintype "power_in"))
      (node (ref "U2") (pin "57") (pinfunction "VBAT_57") (pintype "power_in"))
    )
    (net (code "81") (name "VDD_EXT") (class "Default")
      (node (ref "J4") (pin "7") (pinfunction "7_7") (pintype "bidirectional"))
      (node (ref "Q6") (pin "1") (pinfunction "G_1") (pintype "passive"))
      (node (ref "Q7") (pin "1") (pinfunction "G_1") (pintype "passive"))
      (node (ref "R8") (pin "5") (pinfunction "2_5") (pintype "passive"))
      (node (ref "R8") (pin "6") (pinfunction "2_6") (pintype "passive"))
      (node (ref "U2") (pin "15") (pinfunction "VDD_EXT_15") (pintype "output"))
    )
    (net (code "82") (name "VIN") (class "Default")
      (node (ref "C2") (pin "+") (pinfunction "+_+") (pintype "passive"))
      (node (ref "C24") (pin "2") (pinfunction "2_2") (pintype "passive"))
      (node (ref "D1") (pin "-") (pinfunction "-_-") (pintype "passive"))
      (node (ref "D2") (pin "-") (pinfunction "-_-") (pintype "passive"))
      (node (ref "R4") (pin "2") (pinfunction "2_2") (pintype "passive"))
      (node (ref "T_EXT") (pin "T") (pinfunction "T_T") (pintype "bidirectional"))
      (node (ref "U1") (pin "2") (pinfunction "VIN_2") (pintype "input"))
    )
    (net (code "83") (name "VRTC") (class "Default")
      (node (ref "C6") (pin "2") (pinfunction "2_2") (pintype "passive"))
      (node (ref "J1") (pin "+") (pinfunction "V+_+") (pintype "bidirectional"))
      (node (ref "U2") (pin "26") (pinfunction "VRTC_26") (pintype "bidirectional"))
    )
    (net (code "84") (name "unconnected-(J6-Pad5)") (class "Default")
      (node (ref "J6") (pin "5") (pinfunction "5_5") (pintype "bidirectional"))
    )
    (net (code "85") (name "unconnected-(J6-Pad6)") (class "Default")
      (node (ref "J6") (pin "6") (pinfunction "6_6") (pintype "bidirectional"))
    )
    (net (code "86") (name "unconnected-(J6-Pad7)") (class "Default")
      (node (ref "J6") (pin "7") (pinfunction "7_7") (pintype "bidirectional"))
    )
    (net (code "87") (name "unconnected-(J6-Pad8)") (class "Default")
      (node (ref "J6") (pin "8") (pinfunction "8_8") (pintype "bidirectional"))
    )
    (net (code "88") (name "unconnected-(SIMHOLDER-VPP-Pad5)") (class "Default")
      (node (ref "SIMHOLDER") (pin "5") (pinfunction "VPP_5") (pintype "bidirectional"))
    )
    (net (code "89") (name "unconnected-(U1-NC-Pad1)") (class "Default")
      (node (ref "U1") (pin "1") (pinfunction "NC_1") (pintype "no_connect"))
    )
    (net (code "90") (name "unconnected-(U1-NC-Pad6)") (class "Default")
      (node (ref "U1") (pin "6") (pinfunction "NC_6") (pintype "no_connect"))
    )
    (net (code "91") (name "unconnected-(U1-NC-Pad8)") (class "Default")
      (node (ref "U1") (pin "8") (pinfunction "NC_8") (pintype "no_connect"))
    )
    (net (code "92") (name "unconnected-(U2-NRESET-Pad16)") (class "Default")
      (node (ref "U2") (pin "16") (pinfunction "NRESET_16") (pintype "input"))
    )
    (net (code "93") (name "unconnected-(U2-SCL-Pad38)") (class "Default")
      (node (ref "U2") (pin "38") (pinfunction "SCL_38") (pintype "output"))
    )
    (net (code "94") (name "unconnected-(U2-SDA-Pad37)") (class "Default")
      (node (ref "U2") (pin "37") (pinfunction "SDA_37") (pintype "bidirectional"))
    )
    (net (code "95") (name "unconnected-(U2-SIM_PRESENCE-Pad34)") (class "Default")
      (node (ref "U2") (pin "34") (pinfunction "SIM_PRESENCE_34") (pintype "input"))
    )
    (net (code "96") (name "unconnected-(U4-ADC6-Pad32)") (class "Default")
      (node (ref "U4") (pin "32") (pinfunction "ADC6_32") (pintype "bidirectional"))
    )
    (net (code "97") (name "unconnected-(U4-ADC7-Pad31)") (class "Default")
      (node (ref "U4") (pin "31") (pinfunction "ADC7_31") (pintype "bidirectional"))
    )
    (net (code "98") (name "unconnected-(U4-AREF-Pad16)") (class "Default")
      (node (ref "U4") (pin "16") (pinfunction "AREF_16") (pintype "bidirectional"))
    )
    (net (code "99") (name "unconnected-(U4-GND-Pad35)") (class "Default")
      (node (ref "U4") (pin "35") (pinfunction "GND_35") (pintype "bidirectional"))
    )
    (net (code "100") (name "unconnected-(U4-MISO-Pad38)") (class "Default")
      (node (ref "U4") (pin "38") (pinfunction "MISO_38") (pintype "bidirectional"))
    )
    (net (code "101") (name "unconnected-(U4-MOSI-Pad34)") (class "Default")
      (node (ref "U4") (pin "34") (pinfunction "MOSI_34") (pintype "bidirectional"))
    )
    (net (code "102") (name "unconnected-(U4-PB2{slash}D10{slash}SS{slash}PWM-Pad11)") (class "Default")
      (node (ref "U4") (pin "11") (pinfunction "PB2/D10/SS/PWM_11") (pintype "bidirectional"))
    )
    (net (code "103") (name "unconnected-(U4-PB3{slash}D11{slash}MOSI{slash}PWM-Pad12)") (class "Default")
      (node (ref "U4") (pin "12") (pinfunction "PB3/D11/MOSI/PWM_12") (pintype "bidirectional"))
    )
    (net (code "104") (name "unconnected-(U4-PB4{slash}D12{slash}MISO-Pad13)") (class "Default")
      (node (ref "U4") (pin "13") (pinfunction "PB4/D12/MISO_13") (pintype "bidirectional"))
    )
    (net (code "105") (name "unconnected-(U4-PB5{slash}D13{slash}SCK-Pad14)") (class "Default")
      (node (ref "U4") (pin "14") (pinfunction "PB5/D13/SCK_14") (pintype "bidirectional"))
    )
    (net (code "106") (name "unconnected-(U4-PC0{slash}AD0{slash}D14-Pad19)") (class "Default")
      (node (ref "U4") (pin "19") (pinfunction "PC0/AD0/D14_19") (pintype "bidirectional"))
    )
    (net (code "107") (name "unconnected-(U4-PC1{slash}AD1{slash}D15-Pad20)") (class "Default")
      (node (ref "U4") (pin "20") (pinfunction "PC1/AD1/D15_20") (pintype "bidirectional"))
    )
    (net (code "108") (name "unconnected-(U4-PC2{slash}AD2{slash}D16-Pad21)") (class "Default")
      (node (ref "U4") (pin "21") (pinfunction "PC2/AD2/D16_21") (pintype "bidirectional"))
    )
    (net (code "109") (name "unconnected-(U4-PC3{slash}AD3{slash}D17-Pad22)") (class "Default")
      (node (ref "U4") (pin "22") (pinfunction "PC3/AD3/D17_22") (pintype "bidirectional"))
    )
    (net (code "110") (name "unconnected-(U4-PC4{slash}AD4{slash}D18{slash}SDA-Pad23)") (class "Default")
      (node (ref "U4") (pin "23") (pinfunction "PC4/AD4/D18/SDA_23") (pintype "bidirectional"))
    )
    (net (code "111") (name "unconnected-(U4-PC5{slash}AD5{slash}D19{slash}SCL-Pad24)") (class "Default")
      (node (ref "U4") (pin "24") (pinfunction "PC5/AD5/D19/SCL_24") (pintype "bidirectional"))
    )
    (net (code "112") (name "unconnected-(U4-PD2{slash}D2{slash}INT0-Pad3)") (class "Default")
      (node (ref "U4") (pin "3") (pinfunction "PD2/D2/INT0_3") (pintype "bidirectional"))
    )
    (net (code "113") (name "unconnected-(U4-PD3{slash}D3{slash}INT1{slash}PWM-Pad4)") (class "Default")
      (node (ref "U4") (pin "4") (pinfunction "PD3/D3/INT1/PWM_4") (pintype "bidirectional"))
    )
    (net (code "114") (name "unconnected-(U4-PD4{slash}D4-Pad5)") (class "Default")
      (node (ref "U4") (pin "5") (pinfunction "PD4/D4_5") (pintype "bidirectional"))
    )
    (net (code "115") (name "unconnected-(U4-PD5{slash}D5{slash}PWM-Pad6)") (class "Default")
      (node (ref "U4") (pin "6") (pinfunction "PD5/D5/PWM_6") (pintype "bidirectional"))
    )
    (net (code "116") (name "unconnected-(U4-PD6{slash}D6{slash}PWM-Pad7)") (class "Default")
      (node (ref "U4") (pin "7") (pinfunction "PD6/D6/PWM_7") (pintype "bidirectional"))
    )
    (net (code "117") (name "unconnected-(U4-RESET-Pad30)") (class "Default")
      (node (ref "U4") (pin "30") (pinfunction "RESET_30") (pintype "bidirectional"))
    )
    (net (code "118") (name "unconnected-(U4-RST-Pad36)") (class "Default")
      (node (ref "U4") (pin "36") (pinfunction "RST_36") (pintype "bidirectional"))
    )
    (net (code "119") (name "unconnected-(U4-SCK-Pad37)") (class "Default")
      (node (ref "U4") (pin "37") (pinfunction "SCK_37") (pintype "bidirectional"))
    )
    (net (code "120") (name "unconnected-(U4-SCL-Pad18)") (class "Default")
      (node (ref "U4") (pin "18") (pinfunction "SCL_18") (pintype "bidirectional"))
    )
    (net (code "121") (name "unconnected-(U4-SDA-Pad17)") (class "Default")
      (node (ref "U4") (pin "17") (pinfunction "SDA_17") (pintype "bidirectional"))
    )
    (net (code "122") (name "unconnected-(U4-VCC-Pad33)") (class "Default")
      (node (ref "U4") (pin "33") (pinfunction "VCC_33") (pintype "bidirectional"))
    )
  )
)
